# POVBase.net
KiCad netlist of a schematic drawn in EAGLE
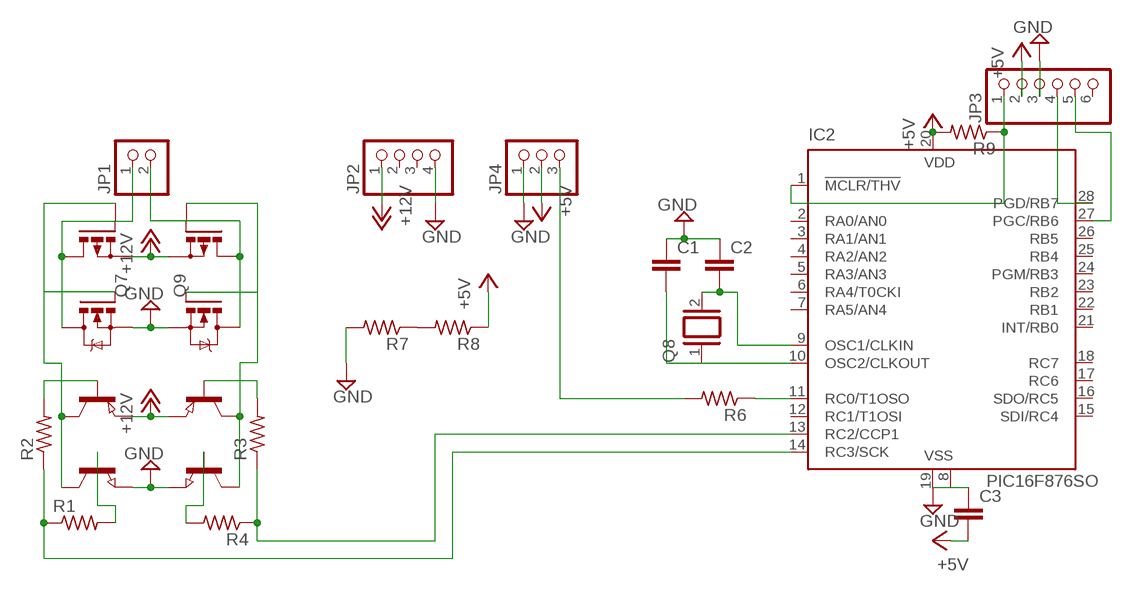
[diagram p0: schematic, sheet 1]

(export (version "E")
  (design (tool "Eeschema 10.0.6"))
  (components
    (comp (ref "C1")
      (value "C-EUC0805")
      (footprint "eagle-import:C0805")
      (libsource (lib "eagle-import") (part "C-EUC0805"))
    )
    (comp (ref "C2")
      (value "C-EUC0805")
      (footprint "eagle-import:C0805")
      (libsource (lib "eagle-import") (part "C-EUC0805"))
    )
    (comp (ref "C3")
      (value "C-EUC0805")
      (footprint "eagle-import:C0805")
      (libsource (lib "eagle-import") (part "C-EUC0805"))
    )
    (comp (ref "IC2")
      (value "PIC16F876SO")
      (footprint "eagle-import:SO28W")
      (fields (field (name "MF") "MICROCHIP") (field (name "MPN") "PIC16F876-20/SO"))
      (libsource (lib "eagle-import") (part "PIC16876SOF"))
    )
    (comp (ref "JP1")
      (value "PINHD-1X2")
      (footprint "eagle-import:1X02")
      (libsource (lib "eagle-import") (part "PINHD-1X2"))
    )
    (comp (ref "JP2")
      (value "PINHD-1X4")
      (footprint "eagle-import:1X04")
      (libsource (lib "eagle-import") (part "PINHD-1X4"))
    )
    (comp (ref "JP3")
      (value "PINHD-1X6")
      (footprint "eagle-import:1X06")
      (libsource (lib "eagle-import") (part "PINHD-1X6"))
    )
    (comp (ref "JP4")
      (value "PINHD-1X3")
      (footprint "eagle-import:1X03")
      (libsource (lib "eagle-import") (part "PINHD-1X3"))
    )
    (comp (ref "Q1")
      (value "NPN-TRANSISTOR_SOT23")
      (footprint "eagle-import:SOT23")
      (libsource (lib "eagle-import") (part "NPN-TRANSISTOR_SOT23"))
    )
    (comp (ref "Q2")
      (value "NPN-TRANSISTOR_SOT23")
      (footprint "eagle-import:SOT23")
      (libsource (lib "eagle-import") (part "NPN-TRANSISTOR_SOT23"))
    )
    (comp (ref "Q3")
      (value "PNP-TRANSISTOR_SOT23")
      (footprint "eagle-import:SOT23")
      (libsource (lib "eagle-import") (part "PNP-TRANSISTOR_SOT23"))
    )
    (comp (ref "Q4")
      (value "PNP-TRANSISTOR_SOT23")
      (footprint "eagle-import:SOT23")
      (libsource (lib "eagle-import") (part "PNP-TRANSISTOR_SOT23"))
    )
    (comp (ref "Q5")
      (value "IRF540")
      (footprint "eagle-import:TO220BV")
      (libsource (lib "eagle-import") (part "IRF540"))
    )
    (comp (ref "Q6")
      (value "IRF540")
      (footprint "eagle-import:TO220BV")
      (libsource (lib "eagle-import") (part "IRF540"))
    )
    (comp (ref "Q7")
      (value "PMOSFET_PTO220BV")
      (footprint "eagle-import:TO220BV")
      (libsource (lib "eagle-import") (part "PMOSFET_PTO220BV"))
    )
    (comp (ref "Q8")
      (value "XTAL/S")
      (footprint "eagle-import:QS")
      (libsource (lib "eagle-import") (part "XTAL/S"))
    )
    (comp (ref "Q9")
      (value "PMOSFET_PTO220BV")
      (footprint "eagle-import:TO220BV")
      (libsource (lib "eagle-import") (part "PMOSFET_PTO220BV"))
    )
    (comp (ref "R1")
      (value "R-US_R0805")
      (footprint "eagle-import:R0805")
      (libsource (lib "eagle-import") (part "R-US_R0805"))
    )
    (comp (ref "R2")
      (value "R-US_R0805")
      (footprint "eagle-import:R0805")
      (libsource (lib "eagle-import") (part "R-US_R0805"))
    )
    (comp (ref "R3")
      (value "R-US_R0805")
      (footprint "eagle-import:R0805")
      (libsource (lib "eagle-import") (part "R-US_R0805"))
    )
    (comp (ref "R4")
      (value "R-US_R0805")
      (footprint "eagle-import:R0805")
      (libsource (lib "eagle-import") (part "R-US_R0805"))
    )
    (comp (ref "R6")
      (value "R-US_R0805")
      (footprint "eagle-import:R0805")
      (libsource (lib "eagle-import") (part "R-US_R0805"))
    )
    (comp (ref "R7")
      (value "R-US_R0805")
      (footprint "eagle-import:R0805")
      (libsource (lib "eagle-import") (part "R-US_R0805"))
    )
    (comp (ref "R8")
      (value "R-US_R0805")
      (footprint "eagle-import:R0805")
      (libsource (lib "eagle-import") (part "R-US_R0805"))
    )
    (comp (ref "R9")
      (value "R-US_R0805")
      (footprint "eagle-import:R0805")
      (libsource (lib "eagle-import") (part "R-US_R0805"))
    )
  )
  (nets
    (net (code "1") (name "+5V") (class "Default")
      (node (ref "C3") (pin "2") (pinfunction "2_2") (pintype "passive"))
      (node (ref "IC2") (pin "20") (pinfunction "VDD_20") (pintype "power_in"))
      (node (ref "JP3") (pin "2") (pinfunction "2_2") (pintype "passive"))
      (node (ref "JP4") (pin "2") (pinfunction "2_2") (pintype "passive"))
      (node (ref "R8") (pin "1") (pinfunction "1_1") (pintype "passive"))
      (node (ref "R9") (pin "2") (pinfunction "2_2") (pintype "passive"))
    )
    (net (code "2") (name "+12V") (class "Default")
      (node (ref "JP2") (pin "1") (pinfunction "1_1") (pintype "passive"))
      (node (ref "Q3") (pin "2") (pinfunction "E_2") (pintype "passive"))
      (node (ref "Q4") (pin "2") (pinfunction "E_2") (pintype "passive"))
      (node (ref "Q7") (pin "S") (pinfunction "S_S") (pintype "passive"))
      (node (ref "Q9") (pin "S") (pinfunction "S_S") (pintype "passive"))
    )
    (net (code "3") (name "GND") (class "Default")
      (node (ref "C1") (pin "1") (pinfunction "1_1") (pintype "passive"))
      (node (ref "C2") (pin "1") (pinfunction "1_1") (pintype "passive"))
      (node (ref "C3") (pin "1") (pinfunction "1_1") (pintype "passive"))
      (node (ref "IC2") (pin "19") (pinfunction "VSS_19") (pintype "power_in"))
      (node (ref "IC2") (pin "8") (pinfunction "VSS_8") (pintype "power_in"))
      (node (ref "JP2") (pin "4") (pinfunction "4_4") (pintype "passive"))
      (node (ref "JP3") (pin "3") (pinfunction "3_3") (pintype "passive"))
      (node (ref "JP4") (pin "1") (pinfunction "1_1") (pintype "passive"))
      (node (ref "Q1") (pin "2") (pinfunction "E_2") (pintype "passive"))
      (node (ref "Q2") (pin "2") (pinfunction "E_2") (pintype "passive"))
      (node (ref "Q5") (pin "S") (pinfunction "S_S") (pintype "passive"))
      (node (ref "Q6") (pin "S") (pinfunction "S_S") (pintype "passive"))
      (node (ref "R7") (pin "2") (pinfunction "2_2") (pintype "passive"))
    )
    (net (code "4") (name "Net-(IC2-OSC1{slash}CLKIN)") (class "Default")
      (node (ref "C2") (pin "2") (pinfunction "2_2") (pintype "passive"))
      (node (ref "IC2") (pin "9") (pinfunction "OSC1/CLKIN_9") (pintype "input"))
      (node (ref "Q8") (pin "2") (pinfunction "2_2") (pintype "passive"))
    )
    (net (code "5") (name "Net-(IC2-OSC2{slash}CLKOUT)") (class "Default")
      (node (ref "C1") (pin "2") (pinfunction "2_2") (pintype "passive"))
      (node (ref "IC2") (pin "10") (pinfunction "OSC2/CLKOUT_10") (pintype "output"))
      (node (ref "Q8") (pin "1") (pinfunction "1_1") (pintype "passive"))
    )
    (net (code "6") (name "Net-(IC2-PGC{slash}RB6)") (class "Default")
      (node (ref "IC2") (pin "27") (pinfunction "PGC/RB6_27") (pintype "bidirectional"))
      (node (ref "JP3") (pin "5") (pinfunction "5_5") (pintype "passive"))
    )
    (net (code "7") (name "Net-(IC2-PGD{slash}RB7)") (class "Default")
      (node (ref "IC2") (pin "28") (pinfunction "PGD/RB7_28") (pintype "bidirectional"))
      (node (ref "JP3") (pin "4") (pinfunction "4_4") (pintype "passive"))
    )
    (net (code "8") (name "Net-(IC2-RC0{slash}T1OSO)") (class "Default")
      (node (ref "IC2") (pin "11") (pinfunction "RC0/T1OSO_11") (pintype "bidirectional"))
      (node (ref "R6") (pin "1") (pinfunction "1_1") (pintype "passive"))
    )
    (net (code "9") (name "Net-(IC2-RC2{slash}CCP1)") (class "Default")
      (node (ref "IC2") (pin "13") (pinfunction "RC2/CCP1_13") (pintype "bidirectional"))
      (node (ref "R3") (pin "1") (pinfunction "1_1") (pintype "passive"))
      (node (ref "R4") (pin "1") (pinfunction "1_1") (pintype "passive"))
    )
    (net (code "10") (name "Net-(IC2-RC3{slash}SCK)") (class "Default")
      (node (ref "IC2") (pin "14") (pinfunction "RC3/SCK_14") (pintype "bidirectional"))
      (node (ref "R1") (pin "1") (pinfunction "1_1") (pintype "passive"))
      (node (ref "R2") (pin "1") (pinfunction "1_1") (pintype "passive"))
    )
    (net (code "11") (name "Net-(IC2-~{MCLR{slash}THV})") (class "Default")
      (node (ref "IC2") (pin "1") (pinfunction "~{MCLR/THV}_1") (pintype "input"))
      (node (ref "JP3") (pin "1") (pinfunction "1_1") (pintype "passive"))
      (node (ref "R9") (pin "1") (pinfunction "1_1") (pintype "passive"))
    )
    (net (code "12") (name "Net-(JP1-Pad1)") (class "Default")
      (node (ref "JP1") (pin "1") (pinfunction "1_1") (pintype "passive"))
      (node (ref "Q5") (pin "D") (pinfunction "D_D") (pintype "passive"))
      (node (ref "Q7") (pin "D") (pinfunction "D_D") (pintype "passive"))
    )
    (net (code "13") (name "Net-(JP1-Pad2)") (class "Default")
      (node (ref "JP1") (pin "2") (pinfunction "2_2") (pintype "passive"))
      (node (ref "Q6") (pin "D") (pinfunction "D_D") (pintype "passive"))
      (node (ref "Q9") (pin "D") (pinfunction "D_D") (pintype "passive"))
    )
    (net (code "14") (name "Net-(JP4-Pad3)") (class "Default")
      (node (ref "JP4") (pin "3") (pinfunction "3_3") (pintype "passive"))
      (node (ref "R6") (pin "2") (pinfunction "2_2") (pintype "passive"))
    )
    (net (code "15") (name "Net-(Q1-B)") (class "Default")
      (node (ref "Q1") (pin "1") (pinfunction "B_1") (pintype "passive"))
      (node (ref "R1") (pin "2") (pinfunction "2_2") (pintype "passive"))
    )
    (net (code "16") (name "Net-(Q1-C)") (class "Default")
      (node (ref "Q1") (pin "3") (pinfunction "C_3") (pintype "passive"))
      (node (ref "Q3") (pin "3") (pinfunction "C_3") (pintype "passive"))
      (node (ref "Q5") (pin "G") (pinfunction "G_G") (pintype "passive"))
      (node (ref "Q7") (pin "G") (pinfunction "G_G") (pintype "passive"))
    )
    (net (code "17") (name "Net-(Q2-B)") (class "Default")
      (node (ref "Q2") (pin "1") (pinfunction "B_1") (pintype "passive"))
      (node (ref "R4") (pin "2") (pinfunction "2_2") (pintype "passive"))
    )
    (net (code "18") (name "Net-(Q2-C)") (class "Default")
      (node (ref "Q2") (pin "3") (pinfunction "C_3") (pintype "passive"))
      (node (ref "Q4") (pin "3") (pinfunction "C_3") (pintype "passive"))
      (node (ref "Q6") (pin "G") (pinfunction "G_G") (pintype "passive"))
      (node (ref "Q9") (pin "G") (pinfunction "G_G") (pintype "passive"))
    )
    (net (code "19") (name "Net-(Q3-B)") (class "Default")
      (node (ref "Q3") (pin "1") (pinfunction "B_1") (pintype "passive"))
      (node (ref "R2") (pin "2") (pinfunction "2_2") (pintype "passive"))
    )
    (net (code "20") (name "Net-(Q4-B)") (class "Default")
      (node (ref "Q4") (pin "1") (pinfunction "B_1") (pintype "passive"))
      (node (ref "R3") (pin "2") (pinfunction "2_2") (pintype "passive"))
    )
    (net (code "21") (name "Net-(R7-Pad1)") (class "Default")
      (node (ref "R7") (pin "1") (pinfunction "1_1") (pintype "passive"))
      (node (ref "R8") (pin "2") (pinfunction "2_2") (pintype "passive"))
    )
    (net (code "22") (name "unconnected-(IC2-INT{slash}RB0-Pad21)") (class "Default")
      (node (ref "IC2") (pin "21") (pinfunction "INT/RB0_21") (pintype "bidirectional"))
    )
    (net (code "23") (name "unconnected-(IC2-PGM{slash}RB3-Pad24)") (class "Default")
      (node (ref "IC2") (pin "24") (pinfunction "PGM/RB3_24") (pintype "bidirectional"))
    )
    (net (code "24") (name "unconnected-(IC2-RA0{slash}AN0-Pad2)") (class "Default")
      (node (ref "IC2") (pin "2") (pinfunction "RA0/AN0_2") (pintype "bidirectional"))
    )
    (net (code "25") (name "unconnected-(IC2-RA1{slash}AN1-Pad3)") (class "Default")
      (node (ref "IC2") (pin "3") (pinfunction "RA1/AN1_3") (pintype "bidirectional"))
    )
    (net (code "26") (name "unconnected-(IC2-RA2{slash}AN2-Pad4)") (class "Default")
      (node (ref "IC2") (pin "4") (pinfunction "RA2/AN2_4") (pintype "bidirectional"))
    )
    (net (code "27") (name "unconnected-(IC2-RA3{slash}AN3-Pad5)") (class "Default")
      (node (ref "IC2") (pin "5") (pinfunction "RA3/AN3_5") (pintype "bidirectional"))
    )
    (net (code "28") (name "unconnected-(IC2-RA4{slash}T0CKI-Pad6)") (class "Default")
      (node (ref "IC2") (pin "6") (pinfunction "RA4/T0CKI_6") (pintype "bidirectional"))
    )
    (net (code "29") (name "unconnected-(IC2-RA5{slash}AN4-Pad7)") (class "Default")
      (node (ref "IC2") (pin "7") (pinfunction "RA5/AN4_7") (pintype "bidirectional"))
    )
    (net (code "30") (name "unconnected-(IC2-RB1-Pad22)") (class "Default")
      (node (ref "IC2") (pin "22") (pinfunction "RB1_22") (pintype "bidirectional"))
    )
    (net (code "31") (name "unconnected-(IC2-RB2-Pad23)") (class "Default")
      (node (ref "IC2") (pin "23") (pinfunction "RB2_23") (pintype "bidirectional"))
    )
    (net (code "32") (name "unconnected-(IC2-RB4-Pad25)") (class "Default")
      (node (ref "IC2") (pin "25") (pinfunction "RB4_25") (pintype "bidirectional"))
    )
    (net (code "33") (name "unconnected-(IC2-RB5-Pad26)") (class "Default")
      (node (ref "IC2") (pin "26") (pinfunction "RB5_26") (pintype "bidirectional"))
    )
    (net (code "34") (name "unconnected-(IC2-RC1{slash}T1OSI-Pad12)") (class "Default")
      (node (ref "IC2") (pin "12") (pinfunction "RC1/T1OSI_12") (pintype "bidirectional"))
    )
    (net (code "35") (name "unconnected-(IC2-RC6-Pad17)") (class "Default")
      (node (ref "IC2") (pin "17") (pinfunction "RC6_17") (pintype "bidirectional"))
    )
    (net (code "36") (name "unconnected-(IC2-RC7-Pad18)") (class "Default")
      (node (ref "IC2") (pin "18") (pinfunction "RC7_18") (pintype "bidirectional"))
    )
    (net (code "37") (name "unconnected-(IC2-SDI{slash}RC4-Pad15)") (class "Default")
      (node (ref "IC2") (pin "15") (pinfunction "SDI/RC4_15") (pintype "bidirectional"))
    )
    (net (code "38") (name "unconnected-(IC2-SDO{slash}RC5-Pad16)") (class "Default")
      (node (ref "IC2") (pin "16") (pinfunction "SDO/RC5_16") (pintype "bidirectional"))
    )
    (net (code "39") (name "unconnected-(JP2-Pad2)") (class "Default")
      (node (ref "JP2") (pin "2") (pinfunction "2_2") (pintype "passive"))
    )
    (net (code "40") (name "unconnected-(JP2-Pad3)") (class "Default")
      (node (ref "JP2") (pin "3") (pinfunction "3_3") (pintype "passive"))
    )
    (net (code "41") (name "unconnected-(JP3-Pad6)") (class "Default")
      (node (ref "JP3") (pin "6") (pinfunction "6_6") (pintype "passive"))
    )
  )
)
